# CapstoneControllerBoard.net
KiCad netlist of a schematic drawn in EAGLE
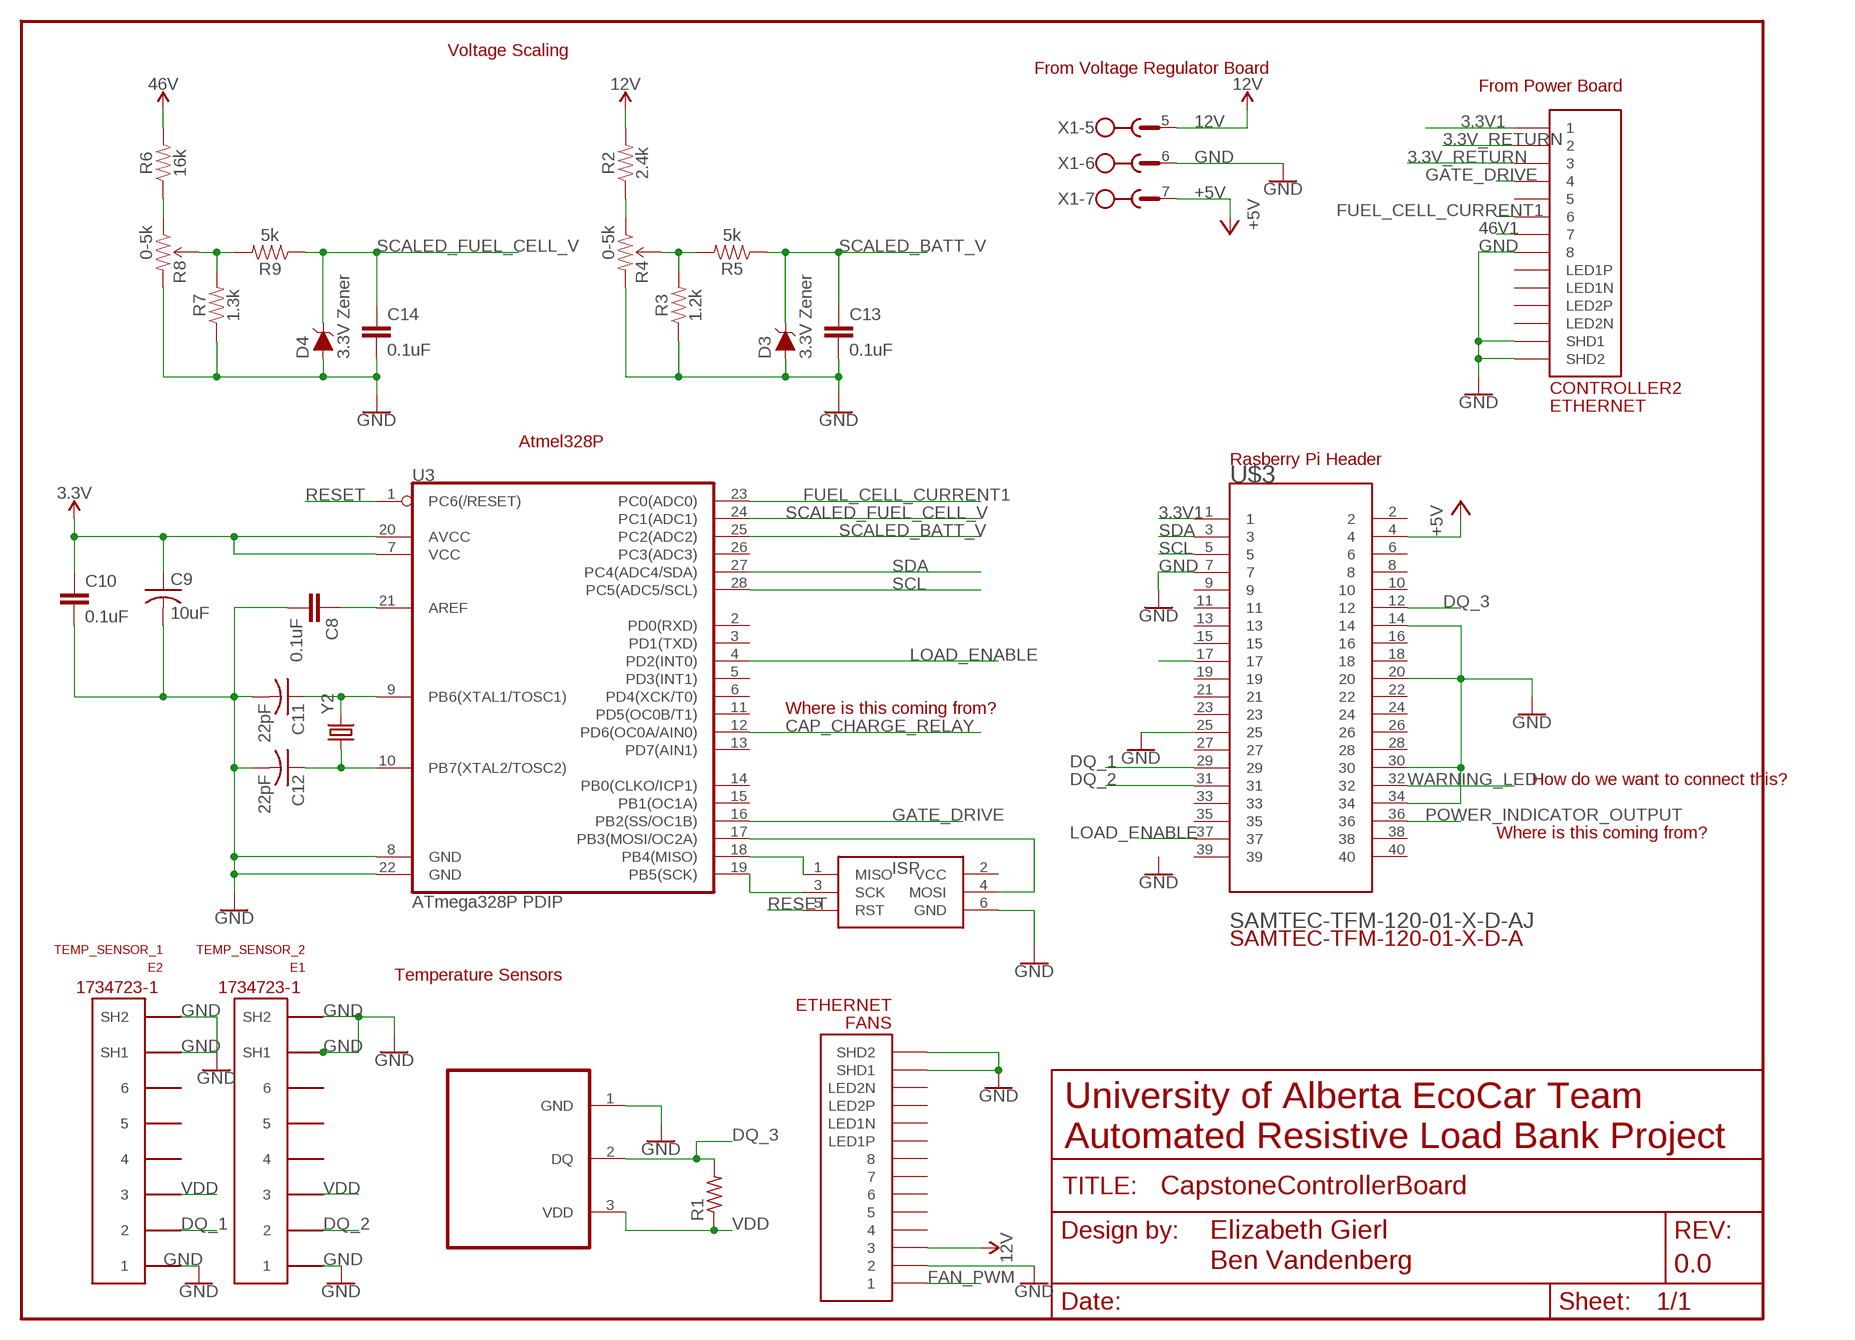
[diagram p0: schematic, sheet 1]

(export (version "E")
  (design (tool "Eeschema 10.0.6"))
  (components
    (comp (ref "C8")
      (value "0.1uF")
      (footprint "eagle-import:0805")
      (libsource (lib "eagle-import") (part "1.0UF-0805-25V-(+80/-20%)"))
    )
    (comp (ref "C9")
      (value "10uF")
      (footprint "eagle-import:C0603")
      (libsource (lib "eagle-import") (part "C-USC0603"))
    )
    (comp (ref "C10")
      (value "0.1uF")
      (footprint "eagle-import:0805")
      (libsource (lib "eagle-import") (part "1.0UF-0805-25V-(+80/-20%)"))
    )
    (comp (ref "C11")
      (value "22pF")
      (footprint "eagle-import:C0603")
      (libsource (lib "eagle-import") (part "C-USC0603"))
    )
    (comp (ref "C12")
      (value "22pF")
      (footprint "eagle-import:C0603")
      (libsource (lib "eagle-import") (part "C-USC0603"))
    )
    (comp (ref "C13")
      (value "0.1uF")
      (footprint "eagle-import:0805")
      (libsource (lib "eagle-import") (part "1.0UF-0805-25V-(+80/-20%)"))
    )
    (comp (ref "C14")
      (value "0.1uF")
      (footprint "eagle-import:0805")
      (libsource (lib "eagle-import") (part "1.0UF-0805-25V-(+80/-20%)"))
    )
    (comp (ref "CONTROLLER2")
      (value "ETHERNET")
      (footprint "eagle-import:A122645-ND")
      (libsource (lib "eagle-import") (part "ETHERNET"))
    )
    (comp (ref "D3")
      (value "3.3V Zener")
      (footprint "eagle-import:DO41-7.6")
      (libsource (lib "eagle-import") (part "SMALL_DIODE"))
    )
    (comp (ref "D4")
      (value "3.3V Zener")
      (footprint "eagle-import:DO41-7.6")
      (libsource (lib "eagle-import") (part "SMALL_DIODE"))
    )
    (comp (ref "E1")
      (value "TEMP_SENSOR_2")
      (footprint "eagle-import:1734723-1_RJ11")
      (libsource (lib "eagle-import") (part "5555140-6"))
    )
    (comp (ref "E2")
      (value "TEMP_SENSOR_1")
      (footprint "eagle-import:1734723-1_RJ11")
      (libsource (lib "eagle-import") (part "5555140-6"))
    )
    (comp (ref "FANS")
      (value "ETHERNET")
      (footprint "eagle-import:A122645-ND")
      (libsource (lib "eagle-import") (part "ETHERNET"))
    )
    (comp (ref "FRAME2")
      (value "FRAME-LETTERNO_PACKAGE")
      (footprint "eagle-import:DUMMY")
      (fields
        (field (name "DESIGNER") "Ben Vandenberg")
        (field (name "DESIGNER_1") "Ben Vandenberg")
        (field (name "REV") "0.0")
      )
      (libsource (lib "eagle-import") (part "FRAME-LETTERNO_PACKAGE"))
    )
    (comp (ref "ISP")
      (value "AVRISP-BOX")
      (footprint "eagle-import:AVRISP-BOX")
      (libsource (lib "eagle-import") (part "AVRISP-BOX"))
    )
    (comp (ref "R1")
      (value "R-US_R0805")
      (footprint "eagle-import:R0805")
      (libsource (lib "eagle-import") (part "R-US_R0805"))
    )
    (comp (ref "R2")
      (value "2.4k")
      (footprint "eagle-import:0805")
      (libsource (lib "eagle-import") (part "0.3OHM-0805-1/8W-1%"))
    )
    (comp (ref "R3")
      (value "1.2k")
      (footprint "eagle-import:0805")
      (libsource (lib "eagle-import") (part "0.3OHM-0805-1/8W-1%"))
    )
    (comp (ref "R4")
      (value "0-5k")
      (footprint "eagle-import:TRIM_POT")
      (libsource (lib "eagle-import") (part "CT6EP502_TRIM_POT"))
    )
    (comp (ref "R5")
      (value "5k")
      (footprint "eagle-import:0805")
      (libsource (lib "eagle-import") (part "0.3OHM-0805-1/8W-1%"))
    )
    (comp (ref "R6")
      (value "16k")
      (footprint "eagle-import:0805")
      (libsource (lib "eagle-import") (part "0.3OHM-0805-1/8W-1%"))
    )
    (comp (ref "R7")
      (value "1.3k")
      (footprint "eagle-import:0805")
      (libsource (lib "eagle-import") (part "0.3OHM-0805-1/8W-1%"))
    )
    (comp (ref "R8")
      (value "0-5k")
      (footprint "eagle-import:TRIM_POT")
      (libsource (lib "eagle-import") (part "CT6EP502_TRIM_POT"))
    )
    (comp (ref "R9")
      (value "5k")
      (footprint "eagle-import:0805")
      (libsource (lib "eagle-import") (part "0.3OHM-0805-1/8W-1%"))
    )
    (comp (ref "U$2")
      (value "DS18B")
      (footprint "eagle-import:TO92")
      (libsource (lib "eagle-import") (part "DS18B"))
    )
    (comp (ref "U$3")
      (value "SAMTEC-TFM-120-01-X-D-AJ")
      (footprint "eagle-import:SAMTEC-TFM-120-01-X-D-A")
      (fields (field (name "MF") "Samtec Inc.") (field (name "MP") "TFM-120-01-S-D-A"))
      (libsource (lib "eagle-import") (part "SAMTEC-TFM-120-01-X-D-AJ"))
    )
    (comp (ref "U3")
      (value "ATmega328P PDIP")
      (footprint "eagle-import:PDIP-T28")
      (libsource (lib "eagle-import") (part "ATMEGA328P_PDIP"))
    )
    (comp (ref "X1")
      (value "MSTBA8")
      (footprint "eagle-import:MSTBA8")
      (fields (field (name "MF") "FARNELL") (field (name "MPN") "1757307"))
      (libsource (lib "eagle-import") (part "MSTBA8"))
    )
    (comp (ref "Y2")
      (value "CRYSTALHC49US")
      (footprint "eagle-import:HC49US")
      (libsource (lib "eagle-import") (part "CRYSTALHC49US"))
    )
  )
  (nets
    (net (code "1") (name "+5V") (class "Default")
      (node (ref "U$3") (pin "4") (pinfunction "4_4") (pintype "passive"))
      (node (ref "X1") (pin "7") (pinfunction "1_7") (pintype "passive"))
    )
    (net (code "2") (name "/3.3V1") (class "Default")
      (node (ref "CONTROLLER2") (pin "P$1") (pinfunction "1_P$1") (pintype "bidirectional"))
      (node (ref "U$3") (pin "1") (pinfunction "1_1") (pintype "passive"))
    )
    (net (code "3") (name "/3.3V_RETURN") (class "Default")
      (node (ref "CONTROLLER2") (pin "P$2") (pinfunction "2_P$2") (pintype "bidirectional"))
      (node (ref "CONTROLLER2") (pin "P$3") (pinfunction "3_P$3") (pintype "bidirectional"))
    )
    (net (code "4") (name "/46V1") (class "Default")
      (node (ref "CONTROLLER2") (pin "P$7") (pinfunction "7_P$7") (pintype "bidirectional"))
    )
    (net (code "5") (name "/CAP_CHARGE_RELAY") (class "Default")
      (node (ref "U3") (pin "12") (pinfunction "PD6(OC0A/AIN0)_12") (pintype "passive"))
    )
    (net (code "6") (name "/DQ_1") (class "Default")
      (node (ref "E2") (pin "2") (pinfunction "2_2") (pintype "bidirectional"))
      (node (ref "U$3") (pin "29") (pinfunction "29_29") (pintype "passive"))
    )
    (net (code "7") (name "/DQ_2") (class "Default")
      (node (ref "E1") (pin "2") (pinfunction "2_2") (pintype "bidirectional"))
      (node (ref "U$3") (pin "31") (pinfunction "31_31") (pintype "passive"))
    )
    (net (code "8") (name "/DQ_3") (class "Default")
      (node (ref "R1") (pin "2") (pinfunction "2_2") (pintype "passive"))
      (node (ref "U$2") (pin "2") (pinfunction "DQ_2") (pintype "bidirectional"))
      (node (ref "U$3") (pin "12") (pinfunction "12_12") (pintype "passive"))
    )
    (net (code "9") (name "/FAN_PWM") (class "Default")
      (node (ref "FANS") (pin "P$1") (pinfunction "1_P$1") (pintype "bidirectional"))
    )
    (net (code "10") (name "/FUEL_CELL_CURRENT1") (class "Default")
      (node (ref "CONTROLLER2") (pin "P$6") (pinfunction "6_P$6") (pintype "bidirectional"))
      (node (ref "U3") (pin "23") (pinfunction "PC0(ADC0)_23") (pintype "passive"))
    )
    (net (code "11") (name "/GATE_DRIVE") (class "Default")
      (node (ref "CONTROLLER2") (pin "P$4") (pinfunction "4_P$4") (pintype "bidirectional"))
      (node (ref "U3") (pin "16") (pinfunction "PB2(SS/OC1B)_16") (pintype "passive"))
    )
    (net (code "12") (name "/LOAD_ENABLE") (class "Default")
      (node (ref "U$3") (pin "37") (pinfunction "37_37") (pintype "passive"))
      (node (ref "U3") (pin "4") (pinfunction "PD2(INT0)_4") (pintype "passive"))
    )
    (net (code "13") (name "/POWER_INDICATOR_OUTPUT") (class "Default")
      (node (ref "U$3") (pin "36") (pinfunction "36_36") (pintype "passive"))
    )
    (net (code "14") (name "/RESET") (class "Default")
      (node (ref "ISP") (pin "5") (pinfunction "RST_5") (pintype "output"))
      (node (ref "U3") (pin "1") (pinfunction "PC6(/RESET)_1") (pintype "passive"))
    )
    (net (code "15") (name "/SCALED_BATT_V") (class "Default")
      (node (ref "C13") (pin "1") (pinfunction "1_1") (pintype "passive"))
      (node (ref "D3") (pin "C") (pinfunction "C_C") (pintype "passive"))
      (node (ref "R5") (pin "1") (pinfunction "1_1") (pintype "passive"))
      (node (ref "U3") (pin "25") (pinfunction "PC2(ADC2)_25") (pintype "passive"))
    )
    (net (code "16") (name "/SCALED_FUEL_CELL_V") (class "Default")
      (node (ref "C14") (pin "1") (pinfunction "1_1") (pintype "passive"))
      (node (ref "D4") (pin "C") (pinfunction "C_C") (pintype "passive"))
      (node (ref "R9") (pin "1") (pinfunction "1_1") (pintype "passive"))
      (node (ref "U3") (pin "24") (pinfunction "PC1(ADC1)_24") (pintype "passive"))
    )
    (net (code "17") (name "/SCL") (class "Default")
      (node (ref "U$3") (pin "5") (pinfunction "5_5") (pintype "passive"))
      (node (ref "U3") (pin "28") (pinfunction "PC5(ADC5/SCL)_28") (pintype "passive"))
    )
    (net (code "18") (name "/SDA") (class "Default")
      (node (ref "U$3") (pin "3") (pinfunction "3_3") (pintype "passive"))
      (node (ref "U3") (pin "27") (pinfunction "PC4(ADC4/SDA)_27") (pintype "passive"))
    )
    (net (code "19") (name "/VCC") (class "Default")
      (node (ref "ISP") (pin "2") (pinfunction "VCC_2") (pintype "power_in"))
    )
    (net (code "20") (name "/VDD") (class "Default")
      (node (ref "E1") (pin "3") (pinfunction "3_3") (pintype "bidirectional"))
      (node (ref "E2") (pin "3") (pinfunction "3_3") (pintype "bidirectional"))
      (node (ref "R1") (pin "1") (pinfunction "1_1") (pintype "passive"))
      (node (ref "U$2") (pin "3") (pinfunction "VDD_3") (pintype "bidirectional"))
    )
    (net (code "21") (name "/WARNING_LED") (class "Default")
      (node (ref "U$3") (pin "32") (pinfunction "32_32") (pintype "passive"))
    )
    (net (code "22") (name "3.3V") (class "Default")
      (node (ref "C10") (pin "1") (pinfunction "1_1") (pintype "passive"))
      (node (ref "C9") (pin "1") (pinfunction "1_1") (pintype "passive"))
      (node (ref "U3") (pin "20") (pinfunction "AVCC_20") (pintype "input"))
      (node (ref "U3") (pin "7") (pinfunction "VCC_7") (pintype "input"))
    )
    (net (code "23") (name "12V") (class "Default")
      (node (ref "FANS") (pin "P$3") (pinfunction "3_P$3") (pintype "bidirectional"))
      (node (ref "R2") (pin "2") (pinfunction "2_2") (pintype "passive"))
      (node (ref "X1") (pin "5") (pinfunction "1_5") (pintype "passive"))
    )
    (net (code "24") (name "46V") (class "Default")
      (node (ref "R6") (pin "2") (pinfunction "2_2") (pintype "passive"))
    )
    (net (code "25") (name "GND") (class "Default")
      (node (ref "C10") (pin "2") (pinfunction "2_2") (pintype "passive"))
      (node (ref "C11") (pin "2") (pinfunction "2_2") (pintype "passive"))
      (node (ref "C12") (pin "2") (pinfunction "2_2") (pintype "passive"))
      (node (ref "C13") (pin "2") (pinfunction "2_2") (pintype "passive"))
      (node (ref "C14") (pin "2") (pinfunction "2_2") (pintype "passive"))
      (node (ref "C8") (pin "2") (pinfunction "2_2") (pintype "passive"))
      (node (ref "C9") (pin "2") (pinfunction "2_2") (pintype "passive"))
      (node (ref "CONTROLLER2") (pin "P$13") (pinfunction "SHD1_P$13") (pintype "bidirectional"))
      (node (ref "CONTROLLER2") (pin "P$14") (pinfunction "SHD2_P$14") (pintype "bidirectional"))
      (node (ref "CONTROLLER2") (pin "P$8") (pinfunction "8_P$8") (pintype "bidirectional"))
      (node (ref "D3") (pin "A") (pinfunction "A_A") (pintype "passive"))
      (node (ref "D4") (pin "A") (pinfunction "A_A") (pintype "passive"))
      (node (ref "E1") (pin "1") (pinfunction "1_1") (pintype "bidirectional"))
      (node (ref "E1") (pin "SH1") (pinfunction "SH1_SH1") (pintype "bidirectional"))
      (node (ref "E1") (pin "SH2") (pinfunction "SH2_SH2") (pintype "bidirectional"))
      (node (ref "E2") (pin "1") (pinfunction "1_1") (pintype "bidirectional"))
      (node (ref "E2") (pin "SH1") (pinfunction "SH1_SH1") (pintype "bidirectional"))
      (node (ref "E2") (pin "SH2") (pinfunction "SH2_SH2") (pintype "bidirectional"))
      (node (ref "FANS") (pin "P$13") (pinfunction "SHD1_P$13") (pintype "bidirectional"))
      (node (ref "FANS") (pin "P$14") (pinfunction "SHD2_P$14") (pintype "bidirectional"))
      (node (ref "FANS") (pin "P$2") (pinfunction "2_P$2") (pintype "bidirectional"))
      (node (ref "ISP") (pin "6") (pinfunction "GND_6") (pintype "power_in"))
      (node (ref "R3") (pin "1") (pinfunction "1_1") (pintype "passive"))
      (node (ref "R4") (pin "3") (pinfunction "CW_3") (pintype "passive"))
      (node (ref "R7") (pin "1") (pinfunction "1_1") (pintype "passive"))
      (node (ref "R8") (pin "3") (pinfunction "CW_3") (pintype "passive"))
      (node (ref "U$2") (pin "1") (pinfunction "GND_1") (pintype "bidirectional"))
      (node (ref "U$3") (pin "14") (pinfunction "14_14") (pintype "passive"))
      (node (ref "U$3") (pin "20") (pinfunction "20_20") (pintype "passive"))
      (node (ref "U$3") (pin "25") (pinfunction "25_25") (pintype "passive"))
      (node (ref "U$3") (pin "30") (pinfunction "30_30") (pintype "passive"))
      (node (ref "U$3") (pin "34") (pinfunction "34_34") (pintype "passive"))
      (node (ref "U$3") (pin "7") (pinfunction "7_7") (pintype "passive"))
      (node (ref "U3") (pin "22") (pinfunction "GND_22") (pintype "input"))
      (node (ref "U3") (pin "8") (pinfunction "GND_8") (pintype "input"))
      (node (ref "X1") (pin "6") (pinfunction "1_6") (pintype "passive"))
    )
    (net (code "26") (name "Net-(ISP-MISO)") (class "Default")
      (node (ref "ISP") (pin "1") (pinfunction "MISO_1") (pintype "input"))
      (node (ref "U3") (pin "18") (pinfunction "PB4(MISO)_18") (pintype "passive"))
    )
    (net (code "27") (name "Net-(ISP-MOSI)") (class "Default")
      (node (ref "ISP") (pin "4") (pinfunction "MOSI_4") (pintype "output"))
      (node (ref "U3") (pin "17") (pinfunction "PB3(MOSI/OC2A)_17") (pintype "passive"))
    )
    (net (code "28") (name "Net-(ISP-SCK)") (class "Default")
      (node (ref "ISP") (pin "3") (pinfunction "SCK_3") (pintype "output"))
      (node (ref "U3") (pin "19") (pinfunction "PB5(SCK)_19") (pintype "passive"))
    )
    (net (code "29") (name "Net-(R4-CCW)") (class "Default")
      (node (ref "R2") (pin "1") (pinfunction "1_1") (pintype "passive"))
      (node (ref "R4") (pin "1") (pinfunction "CCW_1") (pintype "passive"))
    )
    (net (code "30") (name "Net-(R4-WIPER)") (class "Default")
      (node (ref "R3") (pin "2") (pinfunction "2_2") (pintype "passive"))
      (node (ref "R4") (pin "2") (pinfunction "WIPER_2") (pintype "passive"))
      (node (ref "R5") (pin "2") (pinfunction "2_2") (pintype "passive"))
    )
    (net (code "31") (name "Net-(R8-CCW)") (class "Default")
      (node (ref "R6") (pin "1") (pinfunction "1_1") (pintype "passive"))
      (node (ref "R8") (pin "1") (pinfunction "CCW_1") (pintype "passive"))
    )
    (net (code "32") (name "Net-(R8-WIPER)") (class "Default")
      (node (ref "R7") (pin "2") (pinfunction "2_2") (pintype "passive"))
      (node (ref "R8") (pin "2") (pinfunction "WIPER_2") (pintype "passive"))
      (node (ref "R9") (pin "2") (pinfunction "2_2") (pintype "passive"))
    )
    (net (code "33") (name "Net-(U3-AREF)") (class "Default")
      (node (ref "C8") (pin "1") (pinfunction "1_1") (pintype "passive"))
      (node (ref "U3") (pin "21") (pinfunction "AREF_21") (pintype "input"))
    )
    (net (code "34") (name "Net-(U3-PB6(XTAL1{slash}TOSC1))") (class "Default")
      (node (ref "C11") (pin "1") (pinfunction "1_1") (pintype "passive"))
      (node (ref "U3") (pin "9") (pinfunction "PB6(XTAL1/TOSC1)_9") (pintype "passive"))
      (node (ref "Y2") (pin "2") (pinfunction "2_2") (pintype "passive"))
    )
    (net (code "35") (name "Net-(U3-PB7(XTAL2{slash}TOSC2))") (class "Default")
      (node (ref "C12") (pin "1") (pinfunction "1_1") (pintype "passive"))
      (node (ref "U3") (pin "10") (pinfunction "PB7(XTAL2/TOSC2)_10") (pintype "passive"))
      (node (ref "Y2") (pin "1") (pinfunction "1_1") (pintype "passive"))
    )
    (net (code "36") (name "unconnected-(CONTROLLER2-5-PadP$5)") (class "Default")
      (node (ref "CONTROLLER2") (pin "P$5") (pinfunction "5_P$5") (pintype "bidirectional"))
    )
    (net (code "37") (name "unconnected-(CONTROLLER2-LED1N-PadP$9)") (class "Default")
      (node (ref "CONTROLLER2") (pin "P$9") (pinfunction "LED1N_P$9") (pintype "bidirectional"))
    )
    (net (code "38") (name "unconnected-(CONTROLLER2-LED1P-PadP$10)") (class "Default")
      (node (ref "CONTROLLER2") (pin "P$10") (pinfunction "LED1P_P$10") (pintype "bidirectional"))
    )
    (net (code "39") (name "unconnected-(CONTROLLER2-LED2N-PadP$11)") (class "Default")
      (node (ref "CONTROLLER2") (pin "P$11") (pinfunction "LED2N_P$11") (pintype "bidirectional"))
    )
    (net (code "40") (name "unconnected-(CONTROLLER2-LED2P-PadP$12)") (class "Default")
      (node (ref "CONTROLLER2") (pin "P$12") (pinfunction "LED2P_P$12") (pintype "bidirectional"))
    )
    (net (code "41") (name "unconnected-(E1-Pad4)") (class "Default")
      (node (ref "E1") (pin "4") (pinfunction "4_4") (pintype "bidirectional"))
    )
    (net (code "42") (name "unconnected-(E1-Pad5)") (class "Default")
      (node (ref "E1") (pin "5") (pinfunction "5_5") (pintype "bidirectional"))
    )
    (net (code "43") (name "unconnected-(E1-Pad6)") (class "Default")
      (node (ref "E1") (pin "6") (pinfunction "6_6") (pintype "bidirectional"))
    )
    (net (code "44") (name "unconnected-(E2-Pad4)") (class "Default")
      (node (ref "E2") (pin "4") (pinfunction "4_4") (pintype "bidirectional"))
    )
    (net (code "45") (name "unconnected-(E2-Pad5)") (class "Default")
      (node (ref "E2") (pin "5") (pinfunction "5_5") (pintype "bidirectional"))
    )
    (net (code "46") (name "unconnected-(E2-Pad6)") (class "Default")
      (node (ref "E2") (pin "6") (pinfunction "6_6") (pintype "bidirectional"))
    )
    (net (code "47") (name "unconnected-(FANS-4-PadP$4)") (class "Default")
      (node (ref "FANS") (pin "P$4") (pinfunction "4_P$4") (pintype "bidirectional"))
    )
    (net (code "48") (name "unconnected-(FANS-5-PadP$5)") (class "Default")
      (node (ref "FANS") (pin "P$5") (pinfunction "5_P$5") (pintype "bidirectional"))
    )
    (net (code "49") (name "unconnected-(FANS-6-PadP$6)") (class "Default")
      (node (ref "FANS") (pin "P$6") (pinfunction "6_P$6") (pintype "bidirectional"))
    )
    (net (code "50") (name "unconnected-(FANS-7-PadP$7)") (class "Default")
      (node (ref "FANS") (pin "P$7") (pinfunction "7_P$7") (pintype "bidirectional"))
    )
    (net (code "51") (name "unconnected-(FANS-8-PadP$8)") (class "Default")
      (node (ref "FANS") (pin "P$8") (pinfunction "8_P$8") (pintype "bidirectional"))
    )
    (net (code "52") (name "unconnected-(FANS-LED1N-PadP$9)") (class "Default")
      (node (ref "FANS") (pin "P$9") (pinfunction "LED1N_P$9") (pintype "bidirectional"))
    )
    (net (code "53") (name "unconnected-(FANS-LED1P-PadP$10)") (class "Default")
      (node (ref "FANS") (pin "P$10") (pinfunction "LED1P_P$10") (pintype "bidirectional"))
    )
    (net (code "54") (name "unconnected-(FANS-LED2N-PadP$11)") (class "Default")
      (node (ref "FANS") (pin "P$11") (pinfunction "LED2N_P$11") (pintype "bidirectional"))
    )
    (net (code "55") (name "unconnected-(FANS-LED2P-PadP$12)") (class "Default")
      (node (ref "FANS") (pin "P$12") (pinfunction "LED2P_P$12") (pintype "bidirectional"))
    )
    (net (code "56") (name "unconnected-(U$3-Pad2)") (class "Default")
      (node (ref "U$3") (pin "2") (pinfunction "2_2") (pintype "passive"))
    )
    (net (code "57") (name "unconnected-(U$3-Pad6)") (class "Default")
      (node (ref "U$3") (pin "6") (pinfunction "6_6") (pintype "passive"))
    )
    (net (code "58") (name "unconnected-(U$3-Pad8)") (class "Default")
      (node (ref "U$3") (pin "8") (pinfunction "8_8") (pintype "passive"))
    )
    (net (code "59") (name "unconnected-(U$3-Pad9)") (class "Default")
      (node (ref "U$3") (pin "9") (pinfunction "9_9") (pintype "passive"))
    )
    (net (code "60") (name "unconnected-(U$3-Pad10)") (class "Default")
      (node (ref "U$3") (pin "10") (pinfunction "10_10") (pintype "passive"))
    )
    (net (code "61") (name "unconnected-(U$3-Pad11)") (class "Default")
      (node (ref "U$3") (pin "11") (pinfunction "11_11") (pintype "passive"))
    )
    (net (code "62") (name "unconnected-(U$3-Pad13)") (class "Default")
      (node (ref "U$3") (pin "13") (pinfunction "13_13") (pintype "passive"))
    )
    (net (code "63") (name "unconnected-(U$3-Pad15)") (class "Default")
      (node (ref "U$3") (pin "15") (pinfunction "15_15") (pintype "passive"))
    )
    (net (code "64") (name "unconnected-(U$3-Pad16)") (class "Default")
      (node (ref "U$3") (pin "16") (pinfunction "16_16") (pintype "passive"))
    )
    (net (code "65") (name "unconnected-(U$3-Pad17)") (class "Default")
      (node (ref "U$3") (pin "17") (pinfunction "17_17") (pintype "passive"))
    )
    (net (code "66") (name "unconnected-(U$3-Pad18)") (class "Default")
      (node (ref "U$3") (pin "18") (pinfunction "18_18") (pintype "passive"))
    )
    (net (code "67") (name "unconnected-(U$3-Pad19)") (class "Default")
      (node (ref "U$3") (pin "19") (pinfunction "19_19") (pintype "passive"))
    )
    (net (code "68") (name "unconnected-(U$3-Pad21)") (class "Default")
      (node (ref "U$3") (pin "21") (pinfunction "21_21") (pintype "passive"))
    )
    (net (code "69") (name "unconnected-(U$3-Pad22)") (class "Default")
      (node (ref "U$3") (pin "22") (pinfunction "22_22") (pintype "passive"))
    )
    (net (code "70") (name "unconnected-(U$3-Pad23)") (class "Default")
      (node (ref "U$3") (pin "23") (pinfunction "23_23") (pintype "passive"))
    )
    (net (code "71") (name "unconnected-(U$3-Pad24)") (class "Default")
      (node (ref "U$3") (pin "24") (pinfunction "24_24") (pintype "passive"))
    )
    (net (code "72") (name "unconnected-(U$3-Pad26)") (class "Default")
      (node (ref "U$3") (pin "26") (pinfunction "26_26") (pintype "passive"))
    )
    (net (code "73") (name "unconnected-(U$3-Pad27)") (class "Default")
      (node (ref "U$3") (pin "27") (pinfunction "27_27") (pintype "passive"))
    )
    (net (code "74") (name "unconnected-(U$3-Pad28)") (class "Default")
      (node (ref "U$3") (pin "28") (pinfunction "28_28") (pintype "passive"))
    )
    (net (code "75") (name "unconnected-(U$3-Pad33)") (class "Default")
      (node (ref "U$3") (pin "33") (pinfunction "33_33") (pintype "passive"))
    )
    (net (code "76") (name "unconnected-(U$3-Pad35)") (class "Default")
      (node (ref "U$3") (pin "35") (pinfunction "35_35") (pintype "passive"))
    )
    (net (code "77") (name "unconnected-(U$3-Pad38)") (class "Default")
      (node (ref "U$3") (pin "38") (pinfunction "38_38") (pintype "passive"))
    )
    (net (code "78") (name "unconnected-(U$3-Pad39)") (class "Default")
      (node (ref "U$3") (pin "39") (pinfunction "39_39") (pintype "passive"))
    )
    (net (code "79") (name "unconnected-(U$3-Pad40)") (class "Default")
      (node (ref "U$3") (pin "40") (pinfunction "40_40") (pintype "passive"))
    )
    (net (code "80") (name "unconnected-(U3-PB0(CLKO{slash}ICP1)-Pad14)") (class "Default")
      (node (ref "U3") (pin "14") (pinfunction "PB0(CLKO/ICP1)_14") (pintype "passive"))
    )
    (net (code "81") (name "unconnected-(U3-PB1(OC1A)-Pad15)") (class "Default")
      (node (ref "U3") (pin "15") (pinfunction "PB1(OC1A)_15") (pintype "passive"))
    )
    (net (code "82") (name "unconnected-(U3-PC3(ADC3)-Pad26)") (class "Default")
      (node (ref "U3") (pin "26") (pinfunction "PC3(ADC3)_26") (pintype "passive"))
    )
    (net (code "83") (name "unconnected-(U3-PD0(RXD)-Pad2)") (class "Default")
      (node (ref "U3") (pin "2") (pinfunction "PD0(RXD)_2") (pintype "passive"))
    )
    (net (code "84") (name "unconnected-(U3-PD1(TXD)-Pad3)") (class "Default")
      (node (ref "U3") (pin "3") (pinfunction "PD1(TXD)_3") (pintype "passive"))
    )
    (net (code "85") (name "unconnected-(U3-PD3(INT1)-Pad5)") (class "Default")
      (node (ref "U3") (pin "5") (pinfunction "PD3(INT1)_5") (pintype "passive"))
    )
    (net (code "86") (name "unconnected-(U3-PD4(XCK{slash}T0)-Pad6)") (class "Default")
      (node (ref "U3") (pin "6") (pinfunction "PD4(XCK/T0)_6") (pintype "passive"))
    )
    (net (code "87") (name "unconnected-(U3-PD5(OC0B{slash}T1)-Pad11)") (class "Default")
      (node (ref "U3") (pin "11") (pinfunction "PD5(OC0B/T1)_11") (pintype "passive"))
    )
    (net (code "88") (name "unconnected-(U3-PD7(AIN1)-Pad13)") (class "Default")
      (node (ref "U3") (pin "13") (pinfunction "PD7(AIN1)_13") (pintype "passive"))
    )
  )
)
